# USBGpibV2.net
KiCad netlist of a schematic drawn in EAGLE
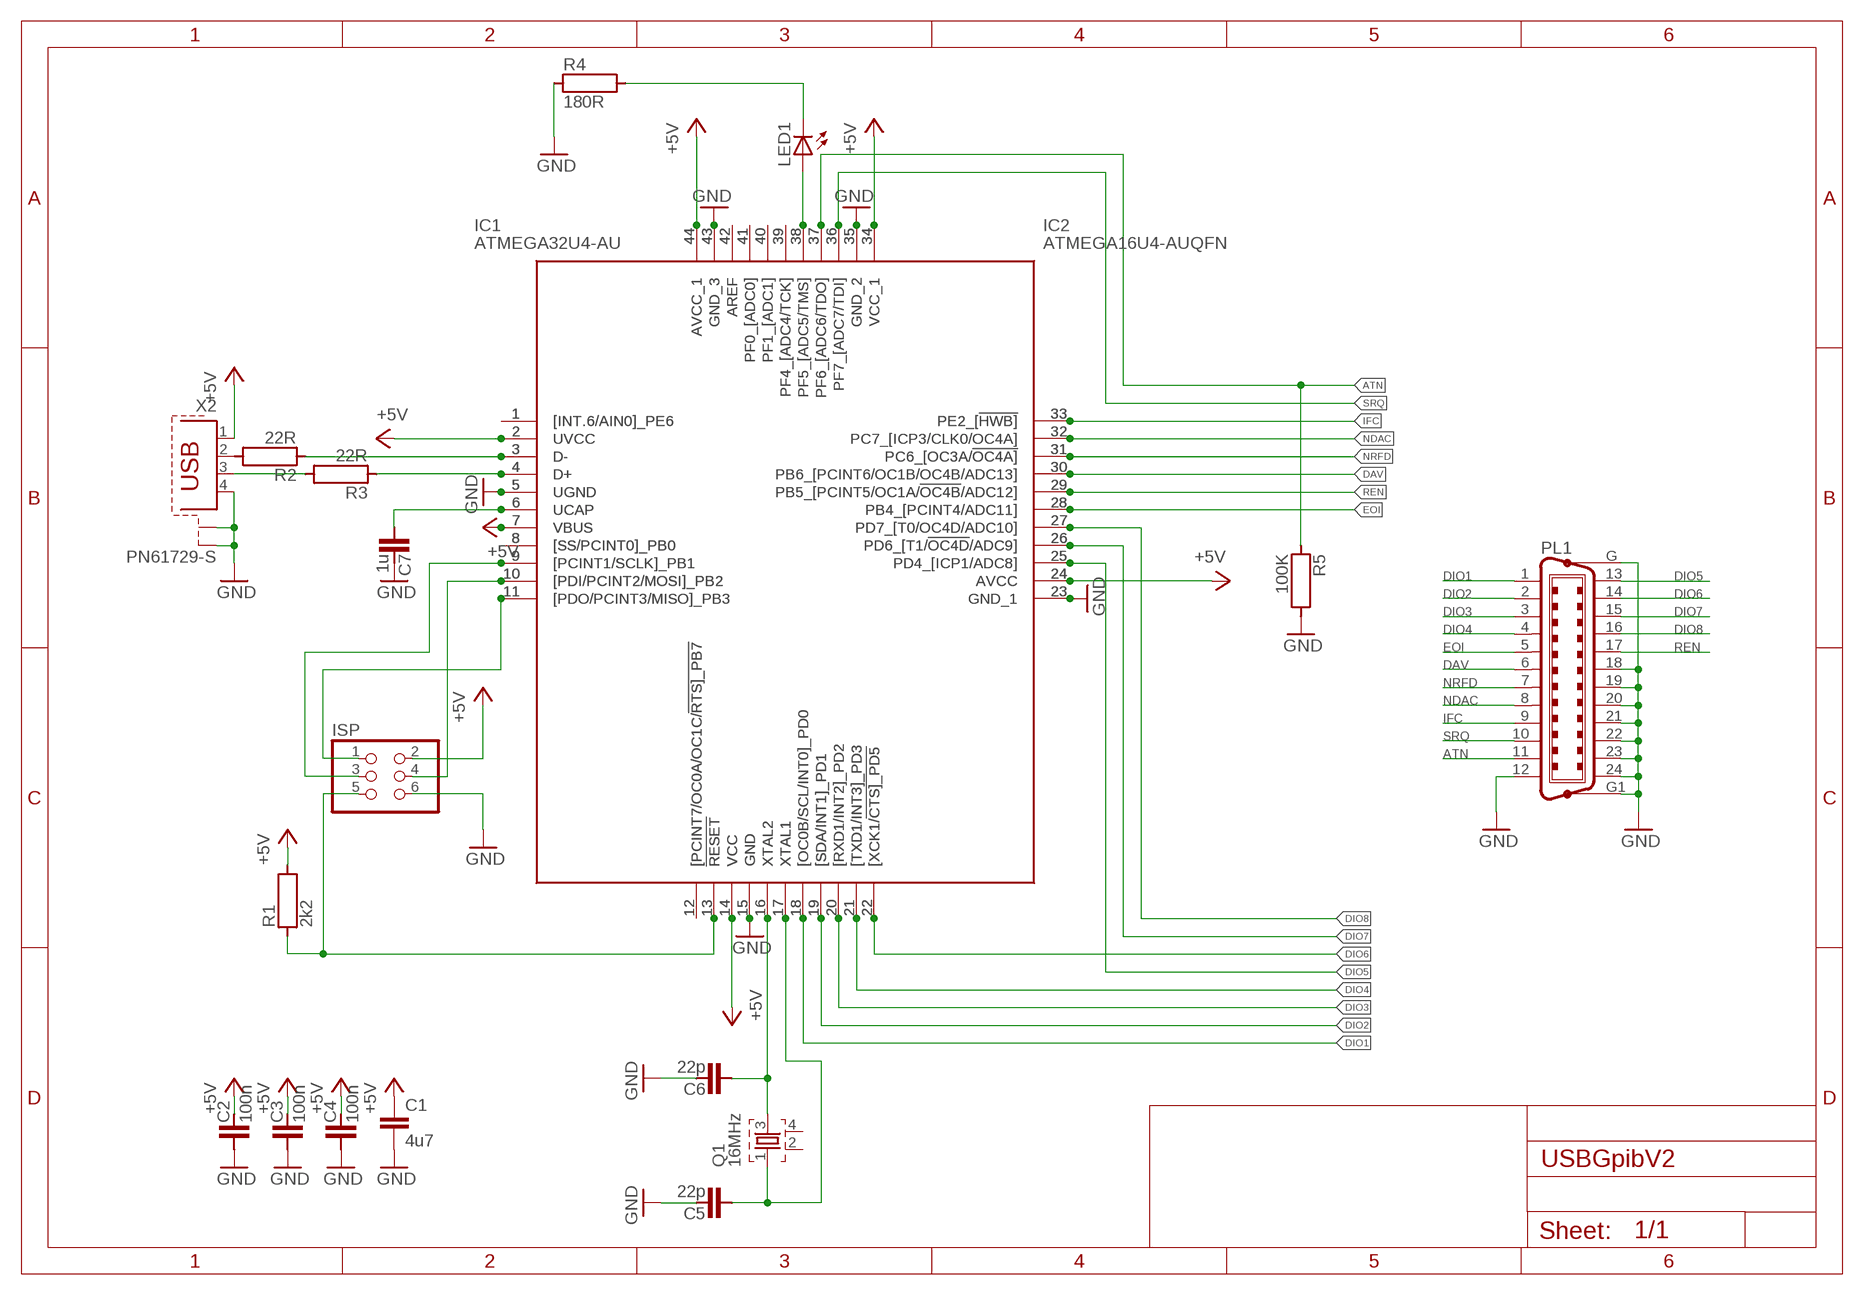
[diagram p0: schematic, sheet 1]

(export (version "E")
  (design (tool "Eeschema 10.0.6"))
  (components
    (comp (ref "C1")
      (value "4u7")
      (footprint "eagle-import:C1206")
      (libsource (lib "eagle-import") (part "C-EUC1206"))
    )
    (comp (ref "C2")
      (value "100n")
      (footprint "eagle-import:C0603")
      (libsource (lib "eagle-import") (part "C0603"))
    )
    (comp (ref "C3")
      (value "100n")
      (footprint "eagle-import:C0603")
      (libsource (lib "eagle-import") (part "C0603"))
    )
    (comp (ref "C4")
      (value "100n")
      (footprint "eagle-import:C0603")
      (libsource (lib "eagle-import") (part "C0603"))
    )
    (comp (ref "C5")
      (value "22p")
      (footprint "eagle-import:C0603")
      (libsource (lib "eagle-import") (part "C0603"))
    )
    (comp (ref "C6")
      (value "22p")
      (footprint "eagle-import:C0603")
      (libsource (lib "eagle-import") (part "C0603"))
    )
    (comp (ref "C7")
      (value "1u")
      (footprint "eagle-import:C0603")
      (libsource (lib "eagle-import") (part "C0603"))
    )
    (comp (ref "IC1")
      (value "ATMEGA32U4-AU")
      (footprint "eagle-import:QFP80P1200X1200X120-44N")
      (fields
        (field (name "MANUFACTURER_PART_NUMBER") "ATMEGA16U4-AU")
        (field (name "MOUSER_PART_NUMBER") "556-ATMEGA16U4-AU")
        (field (name "RS_PART_NUMBER") "1773649P")
      )
      (libsource (lib "eagle-import") (part "ATMEGA16U4-AU"))
    )
    (comp (ref "IC2")
      (value "ATMEGA16U4-AUQFN")
      (footprint "eagle-import:QFN44")
      (libsource (lib "eagle-import") (part "ATMEGA16U4-AUQFN"))
    )
    (comp (ref "ISP")
      (value "PINHD-2X3")
      (footprint "eagle-import:2X03")
      (libsource (lib "eagle-import") (part "PINHD-2X3"))
    )
    (comp (ref "LED1")
      (value "LEDCHIPLED_1206")
      (footprint "eagle-import:CHIPLED_1206")
      (libsource (lib "eagle-import") (part "LEDCHIPLED_1206"))
    )
    (comp (ref "PL1")
      (value "C24HPMALE")
      (footprint "eagle-import:24HP_MALE")
      (libsource (lib "eagle-import") (part "C24HPMALE"))
    )
    (comp (ref "Q1")
      (value "16MHz")
      (footprint "eagle-import:FA-20H")
      (libsource (lib "eagle-import") (part "FA-20H"))
    )
    (comp (ref "R1")
      (value "2k2")
      (footprint "eagle-import:R0603")
      (libsource (lib "eagle-import") (part "R0603"))
    )
    (comp (ref "R2")
      (value "22R")
      (footprint "eagle-import:R0603")
      (libsource (lib "eagle-import") (part "R0603"))
    )
    (comp (ref "R3")
      (value "22R")
      (footprint "eagle-import:R0603")
      (libsource (lib "eagle-import") (part "R0603"))
    )
    (comp (ref "R4")
      (value "180R")
      (footprint "eagle-import:R0603")
      (libsource (lib "eagle-import") (part "R0603"))
    )
    (comp (ref "R5")
      (value "100K")
      (footprint "eagle-import:R0603")
      (libsource (lib "eagle-import") (part "R0603"))
    )
    (comp (ref "X2")
      (value "PN61729-S")
      (footprint "eagle-import:PN61729-S")
      (libsource (lib "eagle-import") (part "PN61729-S"))
    )
  )
  (nets
    (net (code "1") (name "+5V") (class "Default")
      (node (ref "C1") (pin "1") (pinfunction "1_1") (pintype "passive"))
      (node (ref "C2") (pin "2") (pinfunction "2_2") (pintype "passive"))
      (node (ref "C3") (pin "2") (pinfunction "2_2") (pintype "passive"))
      (node (ref "C4") (pin "2") (pinfunction "2_2") (pintype "passive"))
      (node (ref "IC1") (pin "14") (pinfunction "VCC_14") (pintype "power_in"))
      (node (ref "IC1") (pin "2") (pinfunction "UVCC_2") (pintype "power_in"))
      (node (ref "IC1") (pin "24") (pinfunction "AVCC_24") (pintype "power_in"))
      (node (ref "IC1") (pin "34") (pinfunction "VCC_1_34") (pintype "power_in"))
      (node (ref "IC1") (pin "44") (pinfunction "AVCC_1_44") (pintype "power_in"))
      (node (ref "IC1") (pin "7") (pinfunction "VBUS_7") (pintype "bidirectional"))
      (node (ref "IC2") (pin "14") (pinfunction "VCC_14") (pintype "power_in"))
      (node (ref "IC2") (pin "2") (pinfunction "UVCC_2") (pintype "power_in"))
      (node (ref "IC2") (pin "24") (pinfunction "AVCC_24") (pintype "power_in"))
      (node (ref "IC2") (pin "34") (pinfunction "VCC_1_34") (pintype "power_in"))
      (node (ref "IC2") (pin "44") (pinfunction "AVCC_1_44") (pintype "power_in"))
      (node (ref "IC2") (pin "7") (pinfunction "VBUS_7") (pintype "bidirectional"))
      (node (ref "ISP") (pin "2") (pinfunction "2_2") (pintype "passive"))
      (node (ref "R1") (pin "2") (pinfunction "2_2") (pintype "passive"))
      (node (ref "X2") (pin "1") (pinfunction "1_1") (pintype "passive"))
    )
    (net (code "2") (name "ATN") (class "Default")
      (node (ref "IC1") (pin "37") (pinfunction "PF6_[ADC6/TDO]_37") (pintype "bidirectional"))
      (node (ref "IC2") (pin "37") (pinfunction "PF6_[ADC6/TDO]_37") (pintype "bidirectional"))
      (node (ref "PL1") (pin "11") (pinfunction "11_11") (pintype "passive"))
      (node (ref "R5") (pin "1") (pinfunction "1_1") (pintype "passive"))
    )
    (net (code "3") (name "DAV") (class "Default")
      (node (ref "IC1") (pin "30") (pinfunction "PB6_[PCINT6/OC1B/OC4B/ADC13]_30") (pintype "input"))
      (node (ref "IC2") (pin "30") (pinfunction "PB6_[PCINT6/OC1B/OC4B/ADC13]_30") (pintype "input"))
      (node (ref "PL1") (pin "6") (pinfunction "6_6") (pintype "passive"))
    )
    (net (code "4") (name "DIO1") (class "Default")
      (node (ref "IC1") (pin "18") (pinfunction "[OC0B/SCL/INT0]_PD0_18") (pintype "input"))
      (node (ref "IC2") (pin "18") (pinfunction "[OC0B/SCL/INT0]_PD0_18") (pintype "input"))
      (node (ref "PL1") (pin "1") (pinfunction "1_1") (pintype "passive"))
    )
    (net (code "5") (name "DIO2") (class "Default")
      (node (ref "IC1") (pin "19") (pinfunction "[SDA/INT1]_PD1_19") (pintype "input"))
      (node (ref "IC2") (pin "19") (pinfunction "[SDA/INT1]_PD1_19") (pintype "input"))
      (node (ref "PL1") (pin "2") (pinfunction "2_2") (pintype "passive"))
    )
    (net (code "6") (name "DIO3") (class "Default")
      (node (ref "IC1") (pin "20") (pinfunction "[RXD1/INT2]_PD2_20") (pintype "input"))
      (node (ref "IC2") (pin "20") (pinfunction "[RXD1/INT2]_PD2_20") (pintype "input"))
      (node (ref "PL1") (pin "3") (pinfunction "3_3") (pintype "passive"))
    )
    (net (code "7") (name "DIO4") (class "Default")
      (node (ref "IC1") (pin "21") (pinfunction "[TXD1/INT3]_PD3_21") (pintype "input"))
      (node (ref "IC2") (pin "21") (pinfunction "[TXD1/INT3]_PD3_21") (pintype "input"))
      (node (ref "PL1") (pin "4") (pinfunction "4_4") (pintype "passive"))
    )
    (net (code "8") (name "DIO5") (class "Default")
      (node (ref "IC1") (pin "25") (pinfunction "PD4_[ICP1/ADC8]_25") (pintype "bidirectional"))
      (node (ref "IC2") (pin "25") (pinfunction "PD4_[ICP1/ADC8]_25") (pintype "bidirectional"))
      (node (ref "PL1") (pin "13") (pinfunction "13_13") (pintype "passive"))
    )
    (net (code "9") (name "DIO6") (class "Default")
      (node (ref "IC1") (pin "22") (pinfunction "[XCK1/~{CTS]_PD5}_22") (pintype "bidirectional"))
      (node (ref "IC2") (pin "22") (pinfunction "[XCK1/~{CTS]_PD5}_22") (pintype "bidirectional"))
      (node (ref "PL1") (pin "14") (pinfunction "14_14") (pintype "passive"))
    )
    (net (code "10") (name "DIO7") (class "Default")
      (node (ref "IC1") (pin "26") (pinfunction "PD6_[T1/~{OC4D}/ADC9]_26") (pintype "bidirectional"))
      (node (ref "IC2") (pin "26") (pinfunction "PD6_[T1/~{OC4D}/ADC9]_26") (pintype "bidirectional"))
      (node (ref "PL1") (pin "15") (pinfunction "15_15") (pintype "passive"))
    )
    (net (code "11") (name "DIO8") (class "Default")
      (node (ref "IC1") (pin "27") (pinfunction "PD7_[T0/OC4D/ADC10]_27") (pintype "bidirectional"))
      (node (ref "IC2") (pin "27") (pinfunction "PD7_[T0/OC4D/ADC10]_27") (pintype "bidirectional"))
      (node (ref "PL1") (pin "16") (pinfunction "16_16") (pintype "passive"))
    )
    (net (code "12") (name "EOI") (class "Default")
      (node (ref "IC1") (pin "28") (pinfunction "PB4_[PCINT4/ADC11]_28") (pintype "input"))
      (node (ref "IC2") (pin "28") (pinfunction "PB4_[PCINT4/ADC11]_28") (pintype "input"))
      (node (ref "PL1") (pin "5") (pinfunction "5_5") (pintype "passive"))
    )
    (net (code "13") (name "GND") (class "Default")
      (node (ref "C1") (pin "2") (pinfunction "2_2") (pintype "passive"))
      (node (ref "C2") (pin "1") (pinfunction "1_1") (pintype "passive"))
      (node (ref "C3") (pin "1") (pinfunction "1_1") (pintype "passive"))
      (node (ref "C4") (pin "1") (pinfunction "1_1") (pintype "passive"))
      (node (ref "C5") (pin "2") (pinfunction "2_2") (pintype "passive"))
      (node (ref "C6") (pin "2") (pinfunction "2_2") (pintype "passive"))
      (node (ref "C7") (pin "2") (pinfunction "2_2") (pintype "passive"))
      (node (ref "IC1") (pin "15") (pinfunction "GND_15") (pintype "power_in"))
      (node (ref "IC1") (pin "23") (pinfunction "GND_1_23") (pintype "power_in"))
      (node (ref "IC1") (pin "35") (pinfunction "GND_2_35") (pintype "power_in"))
      (node (ref "IC1") (pin "43") (pinfunction "GND_3_43") (pintype "power_in"))
      (node (ref "IC1") (pin "5") (pinfunction "UGND_5") (pintype "power_in"))
      (node (ref "IC2") (pin "15") (pinfunction "GND_15") (pintype "power_in"))
      (node (ref "IC2") (pin "23") (pinfunction "GND_1_23") (pintype "power_in"))
      (node (ref "IC2") (pin "35") (pinfunction "GND_2_35") (pintype "power_in"))
      (node (ref "IC2") (pin "43") (pinfunction "GND_3_43") (pintype "power_in"))
      (node (ref "IC2") (pin "5") (pinfunction "UGND_5") (pintype "power_in"))
      (node (ref "ISP") (pin "6") (pinfunction "6_6") (pintype "passive"))
      (node (ref "PL1") (pin "12") (pinfunction "12_12") (pintype "passive"))
      (node (ref "PL1") (pin "18") (pinfunction "18_18") (pintype "passive"))
      (node (ref "PL1") (pin "19") (pinfunction "19_19") (pintype "passive"))
      (node (ref "PL1") (pin "20") (pinfunction "20_20") (pintype "passive"))
      (node (ref "PL1") (pin "21") (pinfunction "21_21") (pintype "passive"))
      (node (ref "PL1") (pin "22") (pinfunction "22_22") (pintype "passive"))
      (node (ref "PL1") (pin "23") (pinfunction "23_23") (pintype "passive"))
      (node (ref "PL1") (pin "24") (pinfunction "24_24") (pintype "passive"))
      (node (ref "PL1") (pin "G") (pinfunction "G_G") (pintype "passive"))
      (node (ref "PL1") (pin "G1") (pinfunction "G1_G1") (pintype "passive"))
      (node (ref "R4") (pin "1") (pinfunction "1_1") (pintype "passive"))
      (node (ref "R5") (pin "2") (pinfunction "2_2") (pintype "passive"))
      (node (ref "X2") (pin "4") (pinfunction "4_4") (pintype "passive"))
      (node (ref "X2") (pin "S1") (pinfunction "S1_S1") (pintype "passive"))
      (node (ref "X2") (pin "S2") (pinfunction "S2_S2") (pintype "passive"))
    )
    (net (code "14") (name "IFC") (class "Default")
      (node (ref "IC1") (pin "33") (pinfunction "PE2_[~{HWB]}_33") (pintype "bidirectional"))
      (node (ref "IC2") (pin "33") (pinfunction "PE2_[~{HWB]}_33") (pintype "bidirectional"))
      (node (ref "PL1") (pin "9") (pinfunction "9_9") (pintype "passive"))
    )
    (net (code "15") (name "NDAC") (class "Default")
      (node (ref "IC1") (pin "32") (pinfunction "PC7_[ICP3/CLK0/OC4A]_32") (pintype "input"))
      (node (ref "IC2") (pin "32") (pinfunction "PC7_[ICP3/CLK0/OC4A]_32") (pintype "input"))
      (node (ref "PL1") (pin "8") (pinfunction "8_8") (pintype "passive"))
    )
    (net (code "16") (name "NRFD") (class "Default")
      (node (ref "IC1") (pin "31") (pinfunction "PC6_[OC3A/~{OC4A]}_31") (pintype "bidirectional"))
      (node (ref "IC2") (pin "31") (pinfunction "PC6_[OC3A/~{OC4A]}_31") (pintype "bidirectional"))
      (node (ref "PL1") (pin "7") (pinfunction "7_7") (pintype "passive"))
    )
    (net (code "17") (name "Net-(IC1-AREF)") (class "Default")
      (node (ref "IC1") (pin "42") (pinfunction "AREF_42") (pintype "input"))
      (node (ref "IC2") (pin "42") (pinfunction "AREF_42") (pintype "input"))
    )
    (net (code "18") (name "Net-(IC1-D+)") (class "Default")
      (node (ref "IC1") (pin "4") (pinfunction "D+_4") (pintype "bidirectional"))
      (node (ref "IC2") (pin "4") (pinfunction "D+_4") (pintype "bidirectional"))
      (node (ref "R3") (pin "1") (pinfunction "1_1") (pintype "passive"))
    )
    (net (code "19") (name "Net-(IC1-D-)") (class "Default")
      (node (ref "IC1") (pin "3") (pinfunction "D-_3") (pintype "bidirectional"))
      (node (ref "IC2") (pin "3") (pinfunction "D-_3") (pintype "bidirectional"))
      (node (ref "R2") (pin "1") (pinfunction "1_1") (pintype "passive"))
    )
    (net (code "20") (name "Net-(IC1-PF0_[ADC0])") (class "Default")
      (node (ref "IC1") (pin "41") (pinfunction "PF0_[ADC0]_41") (pintype "bidirectional"))
      (node (ref "IC2") (pin "41") (pinfunction "PF0_[ADC0]_41") (pintype "bidirectional"))
    )
    (net (code "21") (name "Net-(IC1-PF1_[ADC1])") (class "Default")
      (node (ref "IC1") (pin "40") (pinfunction "PF1_[ADC1]_40") (pintype "bidirectional"))
      (node (ref "IC2") (pin "40") (pinfunction "PF1_[ADC1]_40") (pintype "bidirectional"))
    )
    (net (code "22") (name "Net-(IC1-PF4_[ADC4{slash}TCK])") (class "Default")
      (node (ref "IC1") (pin "39") (pinfunction "PF4_[ADC4/TCK]_39") (pintype "bidirectional"))
      (node (ref "IC2") (pin "39") (pinfunction "PF4_[ADC4/TCK]_39") (pintype "bidirectional"))
    )
    (net (code "23") (name "Net-(IC1-PF5_[ADC5{slash}TMS])") (class "Default")
      (node (ref "IC1") (pin "38") (pinfunction "PF5_[ADC5/TMS]_38") (pintype "bidirectional"))
      (node (ref "IC2") (pin "38") (pinfunction "PF5_[ADC5/TMS]_38") (pintype "bidirectional"))
      (node (ref "LED1") (pin "A") (pinfunction "A_A") (pintype "passive"))
    )
    (net (code "24") (name "Net-(IC1-UCAP)") (class "Default")
      (node (ref "C7") (pin "1") (pinfunction "1_1") (pintype "passive"))
      (node (ref "IC1") (pin "6") (pinfunction "UCAP_6") (pintype "bidirectional"))
      (node (ref "IC2") (pin "6") (pinfunction "UCAP_6") (pintype "bidirectional"))
    )
    (net (code "25") (name "Net-(IC1-XTAL1)") (class "Default")
      (node (ref "C5") (pin "1") (pinfunction "1_1") (pintype "passive"))
      (node (ref "IC1") (pin "17") (pinfunction "XTAL1_17") (pintype "bidirectional"))
      (node (ref "IC2") (pin "17") (pinfunction "XTAL1_17") (pintype "bidirectional"))
      (node (ref "Q1") (pin "1") (pinfunction "1_1") (pintype "passive"))
    )
    (net (code "26") (name "Net-(IC1-XTAL2)") (class "Default")
      (node (ref "C6") (pin "1") (pinfunction "1_1") (pintype "passive"))
      (node (ref "IC1") (pin "16") (pinfunction "XTAL2_16") (pintype "bidirectional"))
      (node (ref "IC2") (pin "16") (pinfunction "XTAL2_16") (pintype "bidirectional"))
      (node (ref "Q1") (pin "3") (pinfunction "3_3") (pintype "passive"))
    )
    (net (code "27") (name "Net-(IC1-[INT.6{slash}AIN0]_PE6)") (class "Default")
      (node (ref "IC1") (pin "1") (pinfunction "[INT.6/AIN0]_PE6_1") (pintype "input"))
      (node (ref "IC2") (pin "1") (pinfunction "[INT.6/AIN0]_PE6_1") (pintype "input"))
    )
    (net (code "28") (name "Net-(IC1-[PCINT1{slash}SCLK]_PB1)") (class "Default")
      (node (ref "IC1") (pin "9") (pinfunction "[PCINT1/SCLK]_PB1_9") (pintype "input"))
      (node (ref "IC2") (pin "9") (pinfunction "[PCINT1/SCLK]_PB1_9") (pintype "input"))
      (node (ref "ISP") (pin "3") (pinfunction "3_3") (pintype "passive"))
    )
    (net (code "29") (name "Net-(IC1-[PCINT7{slash}OC0A{slash}OC1C{slash}~{RTS]_PB7})") (class "Default")
      (node (ref "IC1") (pin "12") (pinfunction "[PCINT7/OC0A/OC1C/~{RTS]_PB7}_12") (pintype "input"))
      (node (ref "IC2") (pin "12") (pinfunction "[PCINT7/OC0A/OC1C/~{RTS]_PB7}_12") (pintype "input"))
    )
    (net (code "30") (name "Net-(IC1-[PDI{slash}PCINT2{slash}MOSI]_PB2)") (class "Default")
      (node (ref "IC1") (pin "10") (pinfunction "[PDI/PCINT2/MOSI]_PB2_10") (pintype "input"))
      (node (ref "IC2") (pin "10") (pinfunction "[PDI/PCINT2/MOSI]_PB2_10") (pintype "input"))
      (node (ref "ISP") (pin "4") (pinfunction "4_4") (pintype "passive"))
    )
    (net (code "31") (name "Net-(IC1-[PDO{slash}PCINT3{slash}MISO]_PB3)") (class "Default")
      (node (ref "IC1") (pin "11") (pinfunction "[PDO/PCINT3/MISO]_PB3_11") (pintype "input"))
      (node (ref "IC2") (pin "11") (pinfunction "[PDO/PCINT3/MISO]_PB3_11") (pintype "input"))
      (node (ref "ISP") (pin "1") (pinfunction "1_1") (pintype "passive"))
    )
    (net (code "32") (name "Net-(IC1-[SS{slash}PCINT0]_PB0)") (class "Default")
      (node (ref "IC1") (pin "8") (pinfunction "[SS/PCINT0]_PB0_8") (pintype "input"))
      (node (ref "IC2") (pin "8") (pinfunction "[SS/PCINT0]_PB0_8") (pintype "input"))
    )
    (net (code "33") (name "Net-(IC1-~{RESET})") (class "Default")
      (node (ref "IC1") (pin "13") (pinfunction "~{RESET}_13") (pintype "bidirectional"))
      (node (ref "IC2") (pin "13") (pinfunction "~{RESET}_13") (pintype "bidirectional"))
      (node (ref "ISP") (pin "5") (pinfunction "5_5") (pintype "passive"))
      (node (ref "R1") (pin "1") (pinfunction "1_1") (pintype "passive"))
    )
    (net (code "34") (name "Net-(LED1-PadC)") (class "Default")
      (node (ref "LED1") (pin "C") (pinfunction "C_C") (pintype "passive"))
      (node (ref "R4") (pin "2") (pinfunction "2_2") (pintype "passive"))
    )
    (net (code "35") (name "Net-(R2-Pad2)") (class "Default")
      (node (ref "R2") (pin "2") (pinfunction "2_2") (pintype "passive"))
      (node (ref "X2") (pin "2") (pinfunction "2_2") (pintype "passive"))
    )
    (net (code "36") (name "Net-(R3-Pad2)") (class "Default")
      (node (ref "R3") (pin "2") (pinfunction "2_2") (pintype "passive"))
      (node (ref "X2") (pin "3") (pinfunction "3_3") (pintype "passive"))
    )
    (net (code "37") (name "REN") (class "Default")
      (node (ref "IC1") (pin "29") (pinfunction "PB5_[PCINT5/OC1A/~{OC4B}/ADC12]_29") (pintype "input"))
      (node (ref "IC2") (pin "29") (pinfunction "PB5_[PCINT5/OC1A/~{OC4B}/ADC12]_29") (pintype "input"))
      (node (ref "PL1") (pin "17") (pinfunction "17_17") (pintype "passive"))
    )
    (net (code "38") (name "SRQ") (class "Default")
      (node (ref "IC1") (pin "36") (pinfunction "PF7_[ADC7/TDI]_36") (pintype "bidirectional"))
      (node (ref "IC2") (pin "36") (pinfunction "PF7_[ADC7/TDI]_36") (pintype "bidirectional"))
      (node (ref "PL1") (pin "10") (pinfunction "10_10") (pintype "passive"))
    )
    (net (code "39") (name "unconnected-(Q1-Pad2)") (class "Default")
      (node (ref "Q1") (pin "2") (pinfunction "2_2") (pintype "passive"))
    )
    (net (code "40") (name "unconnected-(Q1-Pad4)") (class "Default")
      (node (ref "Q1") (pin "4") (pinfunction "4_4") (pintype "passive"))
    )
  )
)
